# Nixie_PSU.net
KiCad netlist of a schematic drawn in EAGLE
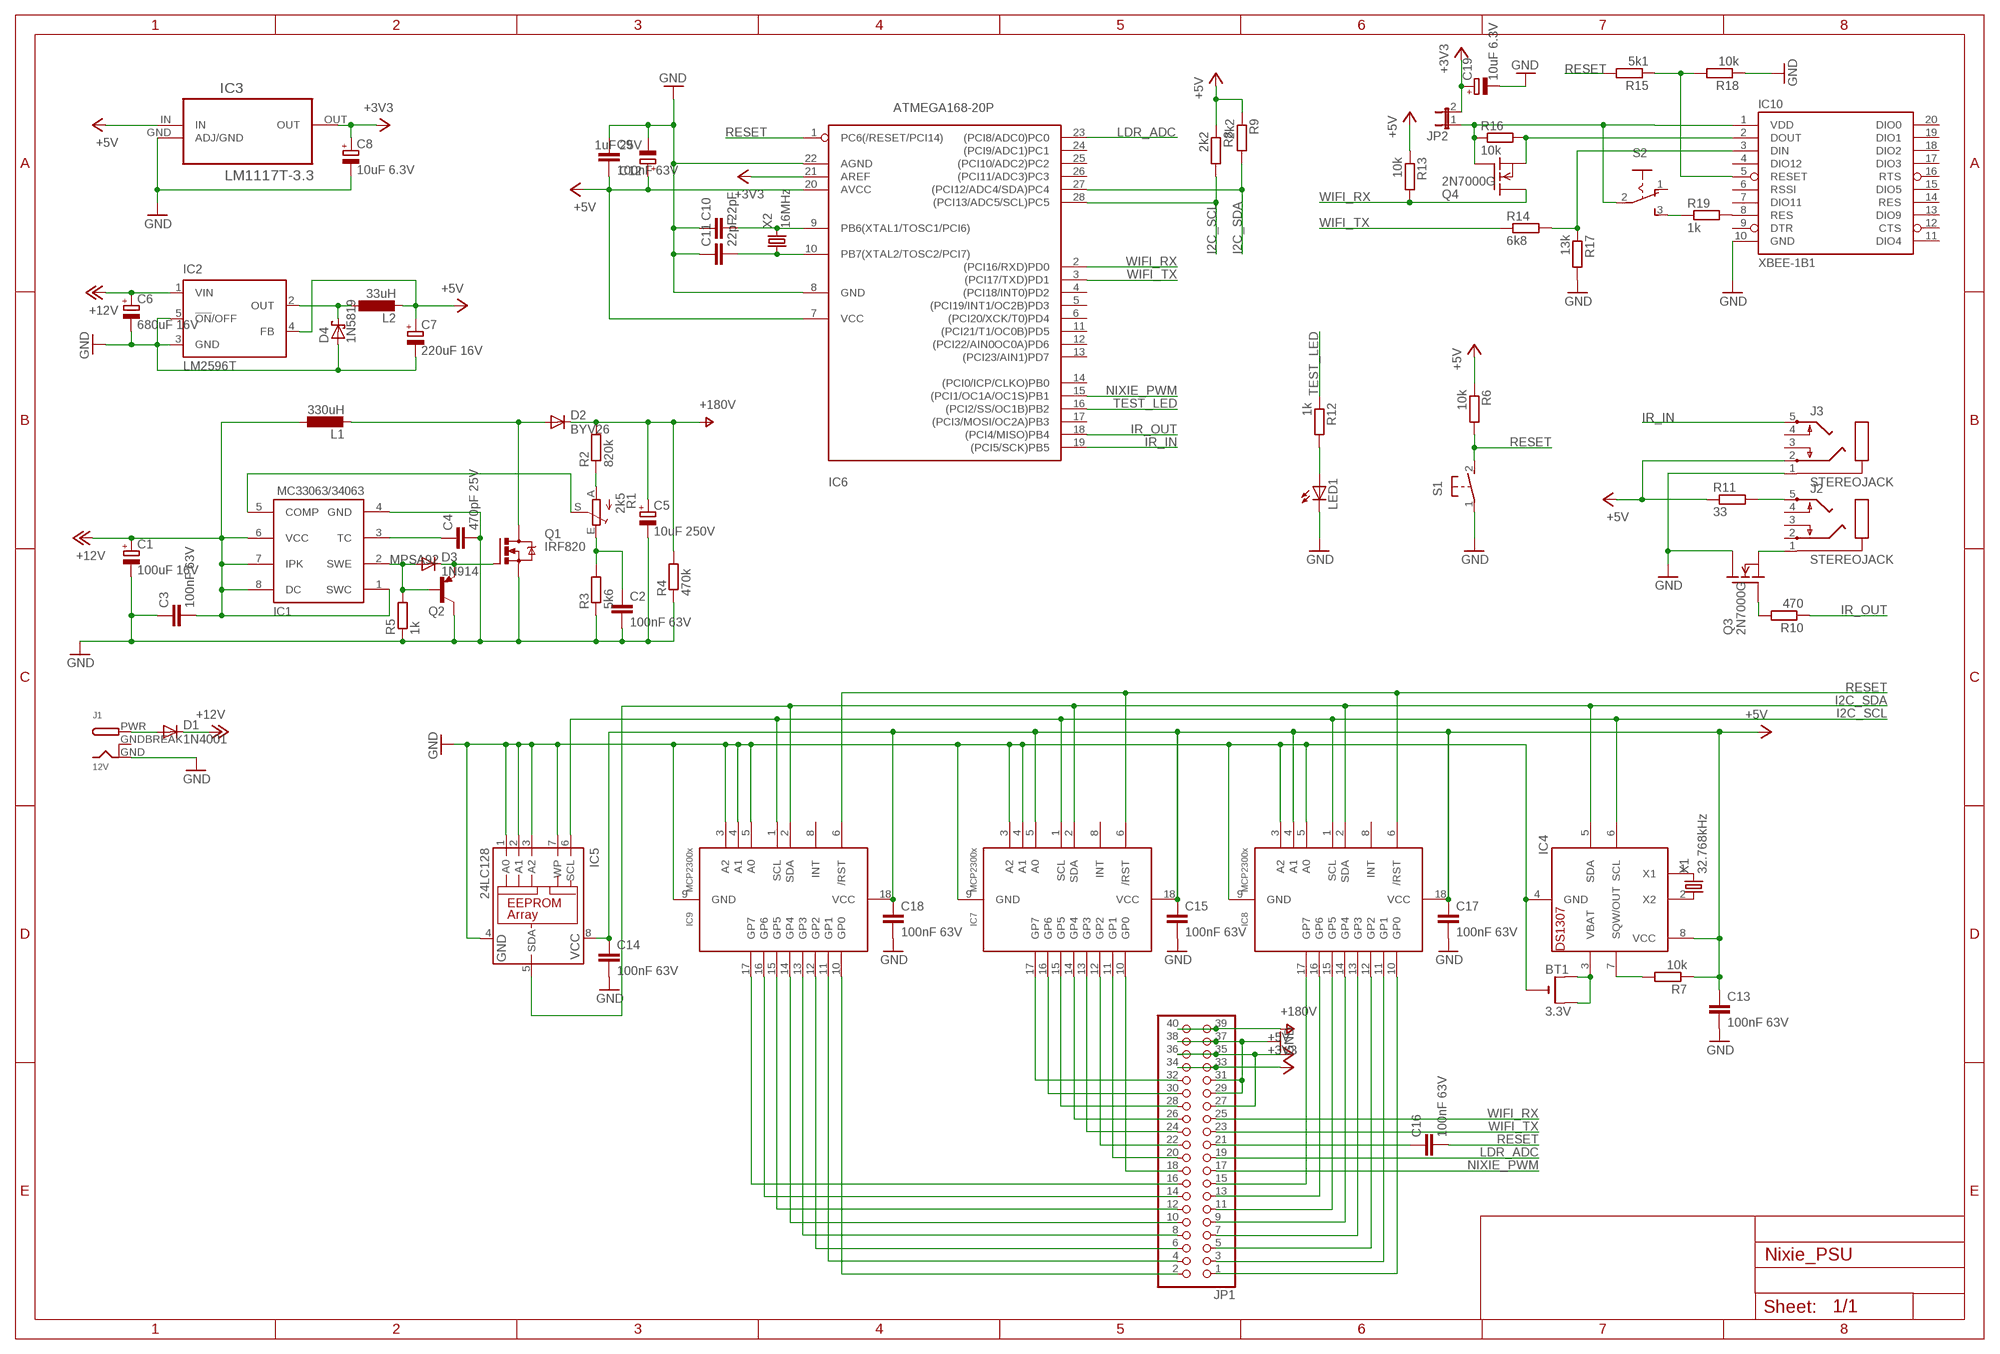
[diagram p0: schematic, sheet 1]

(export (version "E")
  (design (tool "Eeschema 10.0.6"))
  (components
    (comp (ref "BT1")
      (value "3.3V")
      (footprint "eagle-import:CR1220-THM")
      (libsource (lib "eagle-import") (part "CR1220THM"))
    )
    (comp (ref "C1")
      (value "100uF 16V")
      (footprint "eagle-import:E2-5")
      (libsource (lib "eagle-import") (part "CPOL-EUE2-5"))
    )
    (comp (ref "C2")
      (value "100nF 63V")
      (footprint "eagle-import:C050-025X075")
      (libsource (lib "eagle-import") (part "C-EU050-025X075"))
    )
    (comp (ref "C3")
      (value "100nF 63V")
      (footprint "eagle-import:C050-025X075")
      (libsource (lib "eagle-import") (part "C-EU050-025X075"))
    )
    (comp (ref "C4")
      (value "470pF 25V")
      (footprint "eagle-import:C025-025X050")
      (libsource (lib "eagle-import") (part "C-EU025-025X050"))
    )
    (comp (ref "C5")
      (value "10uF 250V")
      (footprint "eagle-import:E5-10,5")
      (libsource (lib "eagle-import") (part "CPOL-EUE5-10.5"))
    )
    (comp (ref "C6")
      (value "680uF 16V")
      (footprint "eagle-import:E3,5-8")
      (libsource (lib "eagle-import") (part "CPOL-EUE3.5-8"))
    )
    (comp (ref "C7")
      (value "220uF 16V")
      (footprint "eagle-import:E2,5-7")
      (libsource (lib "eagle-import") (part "CPOL-EUE2.5-7"))
    )
    (comp (ref "C8")
      (value "10uF 6.3V")
      (footprint "eagle-import:E5-4")
      (libsource (lib "eagle-import") (part "CPOL-EUE5-4"))
    )
    (comp (ref "C9")
      (value "100nF 63V")
      (footprint "eagle-import:C050-025X075")
      (libsource (lib "eagle-import") (part "C-EU050-025X075"))
    )
    (comp (ref "C10")
      (value "22pF")
      (footprint "eagle-import:C025-025X050")
      (libsource (lib "eagle-import") (part "C-EU025-025X050"))
    )
    (comp (ref "C11")
      (value "22pF")
      (footprint "eagle-import:C025-025X050")
      (libsource (lib "eagle-import") (part "C-EU025-025X050"))
    )
    (comp (ref "C12")
      (value "1uF 25V")
      (footprint "eagle-import:E5-4")
      (libsource (lib "eagle-import") (part "CPOL-EUE5-4"))
    )
    (comp (ref "C13")
      (value "100nF 63V")
      (footprint "eagle-import:C050-025X075")
      (libsource (lib "eagle-import") (part "C-EU050-025X075"))
    )
    (comp (ref "C14")
      (value "100nF 63V")
      (footprint "eagle-import:C050-025X075")
      (libsource (lib "eagle-import") (part "C-EU050-025X075"))
    )
    (comp (ref "C15")
      (value "100nF 63V")
      (footprint "eagle-import:C050-025X075")
      (libsource (lib "eagle-import") (part "C-EU050-025X075"))
    )
    (comp (ref "C16")
      (value "100nF 63V")
      (footprint "eagle-import:C050-025X075")
      (libsource (lib "eagle-import") (part "C-EU050-025X075"))
    )
    (comp (ref "C17")
      (value "100nF 63V")
      (footprint "eagle-import:C050-025X075")
      (libsource (lib "eagle-import") (part "C-EU050-025X075"))
    )
    (comp (ref "C18")
      (value "100nF 63V")
      (footprint "eagle-import:C050-025X075")
      (libsource (lib "eagle-import") (part "C-EU050-025X075"))
    )
    (comp (ref "C19")
      (value "10uF 6.3V")
      (footprint "eagle-import:E5-4")
      (libsource (lib "eagle-import") (part "CPOL-EUE5-4"))
    )
    (comp (ref "D1")
      (value "1N4001")
      (footprint "eagle-import:DO41-10")
      (libsource (lib "eagle-import") (part "1N4004"))
    )
    (comp (ref "D2")
      (value "BYV26")
      (footprint "eagle-import:SOD57-10")
      (libsource (lib "eagle-import") (part "BYV27"))
    )
    (comp (ref "D3")
      (value "1N914")
      (footprint "eagle-import:DO34-7")
      (libsource (lib "eagle-import") (part "DIODE-DO34-7"))
    )
    (comp (ref "D4")
      (value "1N5819")
      (footprint "eagle-import:DO41-10")
      (libsource (lib "eagle-import") (part "SCHOTTKY-DIODEDO41"))
    )
    (comp (ref "IC1")
      (value "MC33063/MC34063P")
      (footprint "eagle-import:DIL08")
      (libsource (lib "eagle-import") (part "MC33063/MC34063P"))
    )
    (comp (ref "IC2")
      (value "LM2596T")
      (footprint "eagle-import:T05D")
      (fields (field (name "MPN") "LM2596T-ADJ/LF02"))
      (libsource (lib "eagle-import") (part "LM2596T"))
    )
    (comp (ref "IC3")
      (value "LM1117T-3.3")
      (footprint "eagle-import:TO220BV")
      (libsource (lib "eagle-import") (part "LM1117T-3.3"))
    )
    (comp (ref "IC4")
      (value "DS1307")
      (footprint "eagle-import:DIL08")
      (libsource (lib "eagle-import") (part "DS1307"))
    )
    (comp (ref "IC5")
      (value "24LC128")
      (footprint "eagle-import:DIL08")
      (libsource (lib "eagle-import") (part "24"))
    )
    (comp (ref "IC6")
      (value "ATMEGA168-20P")
      (footprint "eagle-import:DIL28-3")
      (libsource (lib "eagle-import") (part "ATMEGA168P-20"))
    )
    (comp (ref "IC7")
      (value "MCP2300X/P")
      (footprint "eagle-import:DIL18")
      (libsource (lib "eagle-import") (part "MCP2300X/P"))
    )
    (comp (ref "IC8")
      (value "MCP2300X/P")
      (footprint "eagle-import:DIL18")
      (libsource (lib "eagle-import") (part "MCP2300X/P"))
    )
    (comp (ref "IC9")
      (value "MCP2300X/P")
      (footprint "eagle-import:DIL18")
      (libsource (lib "eagle-import") (part "MCP2300X/P"))
    )
    (comp (ref "IC10")
      (value "XBEE-1B1")
      (footprint "eagle-import:XBEE-1")
      (libsource (lib "eagle-import") (part "XBEE-1B1"))
    )
    (comp (ref "J1")
      (value "12V")
      (footprint "eagle-import:DCJACK_2MM_PTH")
      (libsource (lib "eagle-import") (part "DCBARRELPTH"))
    )
    (comp (ref "J2")
      (value "STEREOJACK")
      (footprint "eagle-import:STX3100")
      (libsource (lib "eagle-import") (part "STEREOJACK"))
    )
    (comp (ref "J3")
      (value "STEREOJACK")
      (footprint "eagle-import:STX3100")
      (libsource (lib "eagle-import") (part "STEREOJACK"))
    )
    (comp (ref "JP1")
      (value "PINHD-2X20")
      (footprint "eagle-import:2X20")
      (libsource (lib "eagle-import") (part "PINHD-2X20"))
    )
    (comp (ref "JP2")
      (value "JP1E")
      (footprint "eagle-import:JP1")
      (libsource (lib "eagle-import") (part "JP1E"))
    )
    (comp (ref "L1")
      (value "330uH")
      (footprint "eagle-import:0207_5V")
      (libsource (lib "eagle-import") (part "L-EU0207/5V"))
    )
    (comp (ref "L2")
      (value "33uH")
      (footprint "eagle-import:0207_5V")
      (libsource (lib "eagle-import") (part "L-EU0207/5V"))
    )
    (comp (ref "LED1")
      (value "LED5MM")
      (footprint "eagle-import:LED5MM")
      (libsource (lib "eagle-import") (part "LED5MM"))
    )
    (comp (ref "Q1")
      (value "IRF820")
      (footprint "eagle-import:TO220BV")
      (libsource (lib "eagle-import") (part "IRF540"))
    )
    (comp (ref "Q2")
      (value "MPSA92")
      (footprint "eagle-import:TO92")
      (libsource (lib "eagle-import") (part "-PNP-TO92"))
    )
    (comp (ref "Q3")
      (value "2N7000G")
      (footprint "eagle-import:TO-92")
      (libsource (lib "eagle-import") (part "TN0604N3"))
    )
    (comp (ref "Q4")
      (value "2N7000G")
      (footprint "eagle-import:TO-92")
      (libsource (lib "eagle-import") (part "TN0604N3"))
    )
    (comp (ref "R1")
      (value "2k5")
      (footprint "eagle-import:RJ9W")
      (libsource (lib "eagle-import") (part "TRIM_EU-RJ9W"))
    )
    (comp (ref "R2")
      (value "820k")
      (footprint "eagle-import:0207_10")
      (libsource (lib "eagle-import") (part "R-EU_0207/10"))
    )
    (comp (ref "R3")
      (value "5k6")
      (footprint "eagle-import:0207_10")
      (libsource (lib "eagle-import") (part "R-EU_0207/10"))
    )
    (comp (ref "R4")
      (value "470k")
      (footprint "eagle-import:0207_10")
      (libsource (lib "eagle-import") (part "R-EU_0207/10"))
    )
    (comp (ref "R5")
      (value "1k")
      (footprint "eagle-import:0207_10")
      (libsource (lib "eagle-import") (part "R-EU_0207/10"))
    )
    (comp (ref "R6")
      (value "10k")
      (footprint "eagle-import:0207_10")
      (libsource (lib "eagle-import") (part "R-EU_0207/10"))
    )
    (comp (ref "R7")
      (value "10k")
      (footprint "eagle-import:0207_10")
      (libsource (lib "eagle-import") (part "R-EU_0207/10"))
    )
    (comp (ref "R8")
      (value "2k2")
      (footprint "eagle-import:0207_10")
      (libsource (lib "eagle-import") (part "R-EU_0207/10"))
    )
    (comp (ref "R9")
      (value "2k2")
      (footprint "eagle-import:0207_10")
      (libsource (lib "eagle-import") (part "R-EU_0207/10"))
    )
    (comp (ref "R10")
      (value "470")
      (footprint "eagle-import:0207_10")
      (libsource (lib "eagle-import") (part "R-EU_0207/10"))
    )
    (comp (ref "R11")
      (value "33")
      (footprint "eagle-import:0207_10")
      (libsource (lib "eagle-import") (part "R-EU_0207/10"))
    )
    (comp (ref "R12")
      (value "1k")
      (footprint "eagle-import:0207_10")
      (libsource (lib "eagle-import") (part "R-EU_0207/10"))
    )
    (comp (ref "R13")
      (value "10k")
      (footprint "eagle-import:0207_10")
      (libsource (lib "eagle-import") (part "R-EU_0207/10"))
    )
    (comp (ref "R14")
      (value "6k8")
      (footprint "eagle-import:0207_10")
      (libsource (lib "eagle-import") (part "R-EU_0207/10"))
    )
    (comp (ref "R15")
      (value "5k1")
      (footprint "eagle-import:0207_10")
      (libsource (lib "eagle-import") (part "R-EU_0207/10"))
    )
    (comp (ref "R16")
      (value "10k")
      (footprint "eagle-import:0207_10")
      (libsource (lib "eagle-import") (part "R-EU_0207/10"))
    )
    (comp (ref "R17")
      (value "13k")
      (footprint "eagle-import:0207_10")
      (libsource (lib "eagle-import") (part "R-EU_0207/10"))
    )
    (comp (ref "R18")
      (value "10k")
      (footprint "eagle-import:0207_10")
      (libsource (lib "eagle-import") (part "R-EU_0207/10"))
    )
    (comp (ref "R19")
      (value "1k")
      (footprint "eagle-import:0207_10")
      (libsource (lib "eagle-import") (part "R-EU_0207/10"))
    )
    (comp (ref "S1")
      (value "31-XX")
      (footprint "eagle-import:B3F-31XX")
      (libsource (lib "eagle-import") (part "31-XX"))
    )
    (comp (ref "S2")
      (value "M251")
      (footprint "eagle-import:M251")
      (libsource (lib "eagle-import") (part "M251"))
    )
    (comp (ref "X1")
      (value "32.768kHz")
      (footprint "eagle-import:TC38H")
      (libsource (lib "eagle-import") (part "CRYSTALTC38H"))
    )
    (comp (ref "X2")
      (value "16MHz")
      (footprint "eagle-import:HC18U-V")
      (libsource (lib "eagle-import") (part "CRYSTALHC18U-V"))
    )
  )
  (nets
    (net (code "1") (name "+3V3") (class "Default")
      (node (ref "C19") (pin "+") (pinfunction "+_+") (pintype "passive"))
      (node (ref "C8") (pin "+") (pinfunction "+_+") (pintype "passive"))
      (node (ref "IC3") (pin "OUT") (pinfunction "OUT_OUT") (pintype "output"))
      (node (ref "IC6") (pin "21") (pinfunction "AREF_21") (pintype "bidirectional"))
      (node (ref "JP1") (pin "33") (pinfunction "33_33") (pintype "passive"))
      (node (ref "JP1") (pin "34") (pinfunction "34_34") (pintype "passive"))
      (node (ref "JP2") (pin "2") (pinfunction "2_2") (pintype "passive"))
    )
    (net (code "2") (name "+5V") (class "Default")
      (node (ref "C12") (pin "+") (pinfunction "+_+") (pintype "passive"))
      (node (ref "C13") (pin "1") (pinfunction "1_1") (pintype "passive"))
      (node (ref "C14") (pin "1") (pinfunction "1_1") (pintype "passive"))
      (node (ref "C15") (pin "1") (pinfunction "1_1") (pintype "passive"))
      (node (ref "C17") (pin "1") (pinfunction "1_1") (pintype "passive"))
      (node (ref "C18") (pin "1") (pinfunction "1_1") (pintype "passive"))
      (node (ref "C7") (pin "+") (pinfunction "+_+") (pintype "passive"))
      (node (ref "C9") (pin "2") (pinfunction "2_2") (pintype "passive"))
      (node (ref "IC2") (pin "4") (pinfunction "FB_4") (pintype "input"))
      (node (ref "IC3") (pin "IN") (pinfunction "IN_IN") (pintype "input"))
      (node (ref "IC4") (pin "8") (pinfunction "VCC_8") (pintype "power_in"))
      (node (ref "IC5") (pin "8") (pinfunction "VCC_8") (pintype "power_in"))
      (node (ref "IC6") (pin "20") (pinfunction "AVCC_20") (pintype "bidirectional"))
      (node (ref "IC6") (pin "7") (pinfunction "VCC_7") (pintype "bidirectional"))
      (node (ref "IC7") (pin "18") (pinfunction "VCC_18") (pintype "power_in"))
      (node (ref "IC7") (pin "5") (pinfunction "A0_5") (pintype "input"))
      (node (ref "IC8") (pin "18") (pinfunction "VCC_18") (pintype "power_in"))
      (node (ref "IC8") (pin "4") (pinfunction "A1_4") (pintype "input"))
      (node (ref "IC9") (pin "18") (pinfunction "VCC_18") (pintype "power_in"))
      (node (ref "J3") (pin "2") (pinfunction "2_2") (pintype "passive"))
      (node (ref "JP1") (pin "27") (pinfunction "27_27") (pintype "passive"))
      (node (ref "JP1") (pin "35") (pinfunction "35_35") (pintype "passive"))
      (node (ref "JP1") (pin "36") (pinfunction "36_36") (pintype "passive"))
      (node (ref "L2") (pin "2") (pinfunction "2_2") (pintype "passive"))
      (node (ref "R11") (pin "1") (pinfunction "1_1") (pintype "passive"))
      (node (ref "R13") (pin "1") (pinfunction "1_1") (pintype "passive"))
      (node (ref "R6") (pin "1") (pinfunction "1_1") (pintype "passive"))
      (node (ref "R7") (pin "1") (pinfunction "1_1") (pintype "passive"))
      (node (ref "R8") (pin "1") (pinfunction "1_1") (pintype "passive"))
      (node (ref "R9") (pin "1") (pinfunction "1_1") (pintype "passive"))
    )
    (net (code "3") (name "+12V") (class "Default")
      (node (ref "C1") (pin "+") (pinfunction "+_+") (pintype "passive"))
      (node (ref "C3") (pin "2") (pinfunction "2_2") (pintype "passive"))
      (node (ref "C6") (pin "+") (pinfunction "+_+") (pintype "passive"))
      (node (ref "D1") (pin "C") (pinfunction "C_C") (pintype "passive"))
      (node (ref "IC1") (pin "1") (pinfunction "SWC_1") (pintype "input"))
      (node (ref "IC1") (pin "6") (pinfunction "VCC_6") (pintype "power_in"))
      (node (ref "IC1") (pin "7") (pinfunction "IPK_7") (pintype "bidirectional"))
      (node (ref "IC1") (pin "8") (pinfunction "DC_8") (pintype "input"))
      (node (ref "IC2") (pin "1") (pinfunction "VIN_1") (pintype "input"))
      (node (ref "L1") (pin "1") (pinfunction "1_1") (pintype "passive"))
    )
    (net (code "4") (name "+180V") (class "Default")
      (node (ref "C5") (pin "+") (pinfunction "+_+") (pintype "passive"))
      (node (ref "D2") (pin "C") (pinfunction "C_C") (pintype "passive"))
      (node (ref "JP1") (pin "39") (pinfunction "39_39") (pintype "passive"))
      (node (ref "JP1") (pin "40") (pinfunction "40_40") (pintype "passive"))
      (node (ref "R2") (pin "2") (pinfunction "2_2") (pintype "passive"))
      (node (ref "R4") (pin "2") (pinfunction "2_2") (pintype "passive"))
    )
    (net (code "5") (name "/GNDBREAK") (class "Default")
      (node (ref "J1") (pin "GNDBREAK") (pinfunction "GNDBREAK_GNDBREAK") (pintype "power_in"))
    )
    (net (code "6") (name "/I2C_SCL") (class "Default")
      (node (ref "IC4") (pin "6") (pinfunction "SCL_6") (pintype "bidirectional"))
      (node (ref "IC5") (pin "6") (pinfunction "SCL_6") (pintype "input"))
      (node (ref "IC6") (pin "28") (pinfunction "(PCI13/ADC5/SCL)PC5_28") (pintype "bidirectional"))
      (node (ref "IC7") (pin "1") (pinfunction "SCL_1") (pintype "bidirectional"))
      (node (ref "IC8") (pin "1") (pinfunction "SCL_1") (pintype "bidirectional"))
      (node (ref "IC9") (pin "1") (pinfunction "SCL_1") (pintype "bidirectional"))
      (node (ref "R8") (pin "2") (pinfunction "2_2") (pintype "passive"))
    )
    (net (code "7") (name "/I2C_SDA") (class "Default")
      (node (ref "IC4") (pin "5") (pinfunction "SDA_5") (pintype "bidirectional"))
      (node (ref "IC5") (pin "5") (pinfunction "SDA_5") (pintype "bidirectional"))
      (node (ref "IC6") (pin "27") (pinfunction "(PCI12/ADC4/SDA)PC4_27") (pintype "bidirectional"))
      (node (ref "IC7") (pin "2") (pinfunction "SDA_2") (pintype "bidirectional"))
      (node (ref "IC8") (pin "2") (pinfunction "SDA_2") (pintype "bidirectional"))
      (node (ref "IC9") (pin "2") (pinfunction "SDA_2") (pintype "bidirectional"))
      (node (ref "R9") (pin "2") (pinfunction "2_2") (pintype "passive"))
    )
    (net (code "8") (name "/IR_IN") (class "Default")
      (node (ref "IC6") (pin "19") (pinfunction "(PCI5/SCK)PB5_19") (pintype "bidirectional"))
      (node (ref "J3") (pin "5") (pinfunction "5_5") (pintype "passive"))
    )
    (net (code "9") (name "/IR_OUT") (class "Default")
      (node (ref "IC6") (pin "18") (pinfunction "(PCI4/MISO)PB4_18") (pintype "bidirectional"))
      (node (ref "R10") (pin "1") (pinfunction "1_1") (pintype "passive"))
    )
    (net (code "10") (name "/LDR_ADC") (class "Default")
      (node (ref "IC6") (pin "23") (pinfunction "(PCI8/ADC0)PC0_23") (pintype "bidirectional"))
      (node (ref "JP1") (pin "19") (pinfunction "19_19") (pintype "passive"))
    )
    (net (code "11") (name "/NIXIE_PWM") (class "Default")
      (node (ref "IC6") (pin "15") (pinfunction "(PCI1/OC1A/OC1S)PB1_15") (pintype "bidirectional"))
      (node (ref "JP1") (pin "17") (pinfunction "17_17") (pintype "passive"))
    )
    (net (code "12") (name "/RESET") (class "Default")
      (node (ref "C16") (pin "2") (pinfunction "2_2") (pintype "passive"))
      (node (ref "IC6") (pin "1") (pinfunction "PC6(/RESET/PCI14)_1") (pintype "bidirectional"))
      (node (ref "IC7") (pin "6") (pinfunction "/RST_6") (pintype "input"))
      (node (ref "IC8") (pin "6") (pinfunction "/RST_6") (pintype "input"))
      (node (ref "IC9") (pin "6") (pinfunction "/RST_6") (pintype "input"))
      (node (ref "R15") (pin "2") (pinfunction "2_2") (pintype "passive"))
      (node (ref "R6") (pin "2") (pinfunction "2_2") (pintype "passive"))
      (node (ref "S1") (pin "2") (pinfunction "S_2") (pintype "passive"))
    )
    (net (code "13") (name "/TEST_LED") (class "Default")
      (node (ref "IC6") (pin "16") (pinfunction "(PCI2/SS/OC1B)PB2_16") (pintype "bidirectional"))
      (node (ref "R12") (pin "1") (pinfunction "1_1") (pintype "passive"))
    )
    (net (code "14") (name "/WIFI_RX") (class "Default")
      (node (ref "IC6") (pin "2") (pinfunction "(PCI16/RXD)PD0_2") (pintype "bidirectional"))
      (node (ref "JP1") (pin "25") (pinfunction "25_25") (pintype "passive"))
      (node (ref "Q4") (pin "3") (pinfunction "D_3") (pintype "passive"))
      (node (ref "R13") (pin "2") (pinfunction "2_2") (pintype "passive"))
    )
    (net (code "15") (name "/WIFI_TX") (class "Default")
      (node (ref "IC6") (pin "3") (pinfunction "(PCI17/TXD)PD1_3") (pintype "bidirectional"))
      (node (ref "JP1") (pin "23") (pinfunction "23_23") (pintype "passive"))
      (node (ref "R14") (pin "1") (pinfunction "1_1") (pintype "passive"))
    )
    (net (code "16") (name "GND") (class "Default")
      (node (ref "BT1") (pin "-") (pinfunction "-_-") (pintype "passive"))
      (node (ref "C1") (pin "-") (pinfunction "-_-") (pintype "passive"))
      (node (ref "C10") (pin "1") (pinfunction "1_1") (pintype "passive"))
      (node (ref "C11") (pin "1") (pinfunction "1_1") (pintype "passive"))
      (node (ref "C12") (pin "-") (pinfunction "-_-") (pintype "passive"))
      (node (ref "C13") (pin "2") (pinfunction "2_2") (pintype "passive"))
      (node (ref "C14") (pin "2") (pinfunction "2_2") (pintype "passive"))
      (node (ref "C15") (pin "2") (pinfunction "2_2") (pintype "passive"))
      (node (ref "C17") (pin "2") (pinfunction "2_2") (pintype "passive"))
      (node (ref "C18") (pin "2") (pinfunction "2_2") (pintype "passive"))
      (node (ref "C19") (pin "-") (pinfunction "-_-") (pintype "passive"))
      (node (ref "C2") (pin "2") (pinfunction "2_2") (pintype "passive"))
      (node (ref "C3") (pin "1") (pinfunction "1_1") (pintype "passive"))
      (node (ref "C4") (pin "2") (pinfunction "2_2") (pintype "passive"))
      (node (ref "C5") (pin "-") (pinfunction "-_-") (pintype "passive"))
      (node (ref "C6") (pin "-") (pinfunction "-_-") (pintype "passive"))
      (node (ref "C7") (pin "-") (pinfunction "-_-") (pintype "passive"))
      (node (ref "C8") (pin "-") (pinfunction "-_-") (pintype "passive"))
      (node (ref "C9") (pin "1") (pinfunction "1_1") (pintype "passive"))
      (node (ref "D4") (pin "A") (pinfunction "A_A") (pintype "passive"))
      (node (ref "IC1") (pin "4") (pinfunction "GND_4") (pintype "power_in"))
      (node (ref "IC10") (pin "10") (pinfunction "GND_10") (pintype "power_in"))
      (node (ref "IC2") (pin "3") (pinfunction "GND_3") (pintype "power_in"))
      (node (ref "IC2") (pin "5") (pinfunction "~{ON}/OFF_5") (pintype "input"))
      (node (ref "IC3") (pin "GND") (pinfunction "ADJ/GND_GND") (pintype "passive"))
      (node (ref "IC4") (pin "4") (pinfunction "GND_4") (pintype "power_in"))
      (node (ref "IC5") (pin "1") (pinfunction "A0_1") (pintype "input"))
      (node (ref "IC5") (pin "2") (pinfunction "A1_2") (pintype "input"))
      (node (ref "IC5") (pin "3") (pinfunction "A2_3") (pintype "input"))
      (node (ref "IC5") (pin "4") (pinfunction "GND_4") (pintype "power_in"))
      (node (ref "IC5") (pin "7") (pinfunction "WP_7") (pintype "input"))
      (node (ref "IC6") (pin "22") (pinfunction "AGND_22") (pintype "bidirectional"))
      (node (ref "IC6") (pin "8") (pinfunction "GND_8") (pintype "bidirectional"))
      (node (ref "IC7") (pin "3") (pinfunction "A2_3") (pintype "input"))
      (node (ref "IC7") (pin "4") (pinfunction "A1_4") (pintype "input"))
      (node (ref "IC7") (pin "9") (pinfunction "GND_9") (pintype "power_in"))
      (node (ref "IC8") (pin "3") (pinfunction "A2_3") (pintype "input"))
      (node (ref "IC8") (pin "5") (pinfunction "A0_5") (pintype "input"))
      (node (ref "IC8") (pin "9") (pinfunction "GND_9") (pintype "power_in"))
      (node (ref "IC9") (pin "3") (pinfunction "A2_3") (pintype "input"))
      (node (ref "IC9") (pin "4") (pinfunction "A1_4") (pintype "input"))
      (node (ref "IC9") (pin "5") (pinfunction "A0_5") (pintype "input"))
      (node (ref "IC9") (pin "9") (pinfunction "GND_9") (pintype "power_in"))
      (node (ref "J1") (pin "GND") (pinfunction "GND_GND") (pintype "power_in"))
      (node (ref "J3") (pin "1") (pinfunction "1_1") (pintype "passive"))
      (node (ref "JP1") (pin "29") (pinfunction "29_29") (pintype "passive"))
      (node (ref "JP1") (pin "31") (pinfunction "31_31") (pintype "passive"))
      (node (ref "JP1") (pin "37") (pinfunction "37_37") (pintype "passive"))
      (node (ref "JP1") (pin "38") (pinfunction "38_38") (pintype "passive"))
      (node (ref "LED1") (pin "K") (pinfunction "C_K") (pintype "passive"))
      (node (ref "Q1") (pin "S") (pinfunction "S_S") (pintype "passive"))
      (node (ref "Q2") (pin "3") (pinfunction "C_3") (pintype "passive"))
      (node (ref "Q3") (pin "3") (pinfunction "D_3") (pintype "passive"))
      (node (ref "R17") (pin "2") (pinfunction "2_2") (pintype "passive"))
      (node (ref "R18") (pin "1") (pinfunction "1_1") (pintype "passive"))
      (node (ref "R3") (pin "1") (pinfunction "1_1") (pintype "passive"))
      (node (ref "R4") (pin "1") (pinfunction "1_1") (pintype "passive"))
      (node (ref "R5") (pin "1") (pinfunction "1_1") (pintype "passive"))
      (node (ref "S1") (pin "1") (pinfunction "P_1") (pintype "passive"))
    )
    (net (code "17") (name "Net-(BT1-+)") (class "Default")
      (node (ref "BT1") (pin "+1") (pinfunction "+_+1") (pintype "passive"))
      (node (ref "BT1") (pin "+2") (pinfunction "+1_+2") (pintype "passive"))
      (node (ref "IC4") (pin "3") (pinfunction "VBAT_3") (pintype "power_in"))
    )
    (net (code "18") (name "Net-(C2-Pad1)") (class "Default")
      (node (ref "C2") (pin "1") (pinfunction "1_1") (pintype "passive"))
      (node (ref "R1") (pin "E") (pinfunction "E_E") (pintype "passive"))
      (node (ref "R3") (pin "2") (pinfunction "2_2") (pintype "passive"))
    )
    (net (code "19") (name "Net-(C16-Pad1)") (class "Default")
      (node (ref "C16") (pin "1") (pinfunction "1_1") (pintype "passive"))
      (node (ref "JP1") (pin "21") (pinfunction "21_21") (pintype "passive"))
    )
    (net (code "20") (name "Net-(D1-PadA)") (class "Default")
      (node (ref "D1") (pin "A") (pinfunction "A_A") (pintype "passive"))
      (node (ref "J1") (pin "PWR") (pinfunction "PWR_PWR") (pintype "power_in"))
    )
    (net (code "21") (name "Net-(D2-PadA)") (class "Default")
      (node (ref "D2") (pin "A") (pinfunction "A_A") (pintype "passive"))
      (node (ref "L1") (pin "2") (pinfunction "2_2") (pintype "passive"))
      (node (ref "Q1") (pin "D") (pinfunction "D_D") (pintype "passive"))
    )
    (net (code "22") (name "Net-(IC1-COMP)") (class "Default")
      (node (ref "IC1") (pin "5") (pinfunction "COMP_5") (pintype "input"))
      (node (ref "R1") (pin "S") (pinfunction "S_S") (pintype "passive"))
    )
    (net (code "23") (name "Net-(IC1-SWE)") (class "Default")
      (node (ref "D3") (pin "A") (pinfunction "A_A") (pintype "passive"))
      (node (ref "IC1") (pin "2") (pinfunction "SWE_2") (pintype "input"))
      (node (ref "Q2") (pin "2") (pinfunction "B_2") (pintype "passive"))
      (node (ref "R5") (pin "2") (pinfunction "2_2") (pintype "passive"))
    )
    (net (code "24") (name "Net-(IC1-TC)") (class "Default")
      (node (ref "C4") (pin "1") (pinfunction "1_1") (pintype "passive"))
      (node (ref "IC1") (pin "3") (pinfunction "TC_3") (pintype "input"))
    )
    (net (code "25") (name "Net-(IC2-OUT)") (class "Default")
      (node (ref "D4") (pin "C") (pinfunction "C_C") (pintype "passive"))
      (node (ref "IC2") (pin "2") (pinfunction "OUT_2") (pintype "output"))
      (node (ref "L2") (pin "1") (pinfunction "1_1") (pintype "passive"))
    )
    (net (code "26") (name "Net-(IC4-SQW{slash}OUT)") (class "Default")
      (node (ref "IC4") (pin "7") (pinfunction "SQW/OUT_7") (pintype "bidirectional"))
      (node (ref "R7") (pin "2") (pinfunction "2_2") (pintype "passive"))
    )
    (net (code "27") (name "Net-(IC4-X1)") (class "Default")
      (node (ref "IC4") (pin "1") (pinfunction "X1_1") (pintype "passive"))
      (node (ref "X1") (pin "2") (pinfunction "2_2") (pintype "passive"))
    )
    (net (code "28") (name "Net-(IC4-X2)") (class "Default")
      (node (ref "IC4") (pin "2") (pinfunction "X2_2") (pintype "passive"))
      (node (ref "X1") (pin "1") (pinfunction "1_1") (pintype "passive"))
    )
    (net (code "29") (name "Net-(IC6-PB6(XTAL1{slash}TOSC1{slash}PCI6))") (class "Default")
      (node (ref "C10") (pin "2") (pinfunction "2_2") (pintype "passive"))
      (node (ref "IC6") (pin "9") (pinfunction "PB6(XTAL1/TOSC1/PCI6)_9") (pintype "bidirectional"))
      (node (ref "X2") (pin "2") (pinfunction "2_2") (pintype "passive"))
    )
    (net (code "30") (name "Net-(IC6-PB7(XTAL2{slash}TOSC2{slash}PCI7))") (class "Default")
      (node (ref "C11") (pin "2") (pinfunction "2_2") (pintype "passive"))
      (node (ref "IC6") (pin "10") (pinfunction "PB7(XTAL2/TOSC2/PCI7)_10") (pintype "bidirectional"))
      (node (ref "X2") (pin "1") (pinfunction "1_1") (pintype "passive"))
    )
    (net (code "31") (name "Net-(IC7-GP0)") (class "Default")
      (node (ref "IC7") (pin "10") (pinfunction "GP0_10") (pintype "bidirectional"))
      (node (ref "JP1") (pin "18") (pinfunction "18_18") (pintype "passive"))
    )
    (net (code "32") (name "Net-(IC7-GP1)") (class "Default")
      (node (ref "IC7") (pin "11") (pinfunction "GP1_11") (pintype "bidirectional"))
      (node (ref "JP1") (pin "20") (pinfunction "20_20") (pintype "passive"))
    )
    (net (code "33") (name "Net-(IC7-GP2)") (class "Default")
      (node (ref "IC7") (pin "12") (pinfunction "GP2_12") (pintype "bidirectional"))
      (node (ref "JP1") (pin "22") (pinfunction "22_22") (pintype "passive"))
    )
    (net (code "34") (name "Net-(IC7-GP3)") (class "Default")
      (node (ref "IC7") (pin "13") (pinfunction "GP3_13") (pintype "bidirectional"))
      (node (ref "JP1") (pin "24") (pinfunction "24_24") (pintype "passive"))
    )
    (net (code "35") (name "Net-(IC7-GP4)") (class "Default")
      (node (ref "IC7") (pin "14") (pinfunction "GP4_14") (pintype "bidirectional"))
      (node (ref "JP1") (pin "26") (pinfunction "26_26") (pintype "passive"))
    )
    (net (code "36") (name "Net-(IC7-GP5)") (class "Default")
      (node (ref "IC7") (pin "15") (pinfunction "GP5_15") (pintype "bidirectional"))
      (node (ref "JP1") (pin "28") (pinfunction "28_28") (pintype "passive"))
    )
    (net (code "37") (name "Net-(IC7-GP6)") (class "Default")
      (node (ref "IC7") (pin "16") (pinfunction "GP6_16") (pintype "bidirectional"))
      (node (ref "JP1") (pin "30") (pinfunction "30_30") (pintype "passive"))
    )
    (net (code "38") (name "Net-(IC7-GP7)") (class "Default")
      (node (ref "IC7") (pin "17") (pinfunction "GP7_17") (pintype "bidirectional"))
      (node (ref "JP1") (pin "32") (pinfunction "32_32") (pintype "passive"))
    )
    (net (code "39") (name "Net-(IC8-GP0)") (class "Default")
      (node (ref "IC8") (pin "10") (pinfunction "GP0_10") (pintype "bidirectional"))
      (node (ref "JP1") (pin "1") (pinfunction "1_1") (pintype "passive"))
    )
    (net (code "40") (name "Net-(IC8-GP1)") (class "Default")
      (node (ref "IC8") (pin "11") (pinfunction "GP1_11") (pintype "bidirectional"))
      (node (ref "JP1") (pin "3") (pinfunction "3_3") (pintype "passive"))
    )
    (net (code "41") (name "Net-(IC8-GP2)") (class "Default")
      (node (ref "IC8") (pin "12") (pinfunction "GP2_12") (pintype "bidirectional"))
      (node (ref "JP1") (pin "5") (pinfunction "5_5") (pintype "passive"))
    )
    (net (code "42") (name "Net-(IC8-GP3)") (class "Default")
      (node (ref "IC8") (pin "13") (pinfunction "GP3_13") (pintype "bidirectional"))
      (node (ref "JP1") (pin "7") (pinfunction "7_7") (pintype "passive"))
    )
    (net (code "43") (name "Net-(IC8-GP4)") (class "Default")
      (node (ref "IC8") (pin "14") (pinfunction "GP4_14") (pintype "bidirectional"))
      (node (ref "JP1") (pin "9") (pinfunction "9_9") (pintype "passive"))
    )
    (net (code "44") (name "Net-(IC8-GP5)") (class "Default")
      (node (ref "IC8") (pin "15") (pinfunction "GP5_15") (pintype "bidirectional"))
      (node (ref "JP1") (pin "11") (pinfunction "11_11") (pintype "passive"))
    )
    (net (code "45") (name "Net-(IC8-GP6)") (class "Default")
      (node (ref "IC8") (pin "16") (pinfunction "GP6_16") (pintype "bidirectional"))
      (node (ref "JP1") (pin "13") (pinfunction "13_13") (pintype "passive"))
    )
    (net (code "46") (name "Net-(IC8-GP7)") (class "Default")
      (node (ref "IC8") (pin "17") (pinfunction "GP7_17") (pintype "bidirectional"))
      (node (ref "JP1") (pin "15") (pinfunction "15_15") (pintype "passive"))
    )
    (net (code "47") (name "Net-(IC9-GP0)") (class "Default")
      (node (ref "IC9") (pin "10") (pinfunction "GP0_10") (pintype "bidirectional"))
      (node (ref "JP1") (pin "2") (pinfunction "2_2") (pintype "passive"))
    )
    (net (code "48") (name "Net-(IC9-GP1)") (class "Default")
      (node (ref "IC9") (pin "11") (pinfunction "GP1_11") (pintype "bidirectional"))
      (node (ref "JP1") (pin "4") (pinfunction "4_4") (pintype "passive"))
    )
    (net (code "49") (name "Net-(IC9-GP2)") (class "Default")
      (node (ref "IC9") (pin "12") (pinfunction "GP2_12") (pintype "bidirectional"))
      (node (ref "JP1") (pin "6") (pinfunction "6_6") (pintype "passive"))
    )
    (net (code "50") (name "Net-(IC9-GP3)") (class "Default")
      (node (ref "IC9") (pin "13") (pinfunction "GP3_13") (pintype "bidirectional"))
      (node (ref "JP1") (pin "8") (pinfunction "8_8") (pintype "passive"))
    )
    (net (code "51") (name "Net-(IC9-GP4)") (class "Default")
      (node (ref "IC9") (pin "14") (pinfunction "GP4_14") (pintype "bidirectional"))
      (node (ref "JP1") (pin "10") (pinfunction "10_10") (pintype "passive"))
    )
    (net (code "52") (name "Net-(IC9-GP5)") (class "Default")
      (node (ref "IC9") (pin "15") (pinfunction "GP5_15") (pintype "bidirectional"))
      (node (ref "JP1") (pin "12") (pinfunction "12_12") (pintype "passive"))
    )
    (net (code "53") (name "Net-(IC9-GP6)") (class "Default")
      (node (ref "IC9") (pin "16") (pinfunction "GP6_16") (pintype "bidirectional"))
      (node (ref "JP1") (pin "14") (pinfunction "14_14") (pintype "passive"))
    )
    (net (code "54") (name "Net-(IC9-GP7)") (class "Default")
      (node (ref "IC9") (pin "17") (pinfunction "GP7_17") (pintype "bidirectional"))
      (node (ref "JP1") (pin "16") (pinfunction "16_16") (pintype "passive"))
    )
    (net (code "55") (name "Net-(IC10-DIN)") (class "Default")
      (node (ref "IC10") (pin "3") (pinfunction "DIN_3") (pintype "input"))
      (node (ref "R14") (pin "2") (pinfunction "2_2") (pintype "passive"))
      (node (ref "R17") (pin "1") (pinfunction "1_1") (pintype "passive"))
    )
    (net (code "56") (name "Net-(IC10-DOUT)") (class "Default")
      (node (ref "IC10") (pin "2") (pinfunction "DOUT_2") (pintype "output"))
      (node (ref "Q4") (pin "1") (pinfunction "S_1") (pintype "passive"))
      (node (ref "R16") (pin "2") (pinfunction "2_2") (pintype "passive"))
    )
    (net (code "57") (name "Net-(IC10-RES-Pad8)") (class "Default")
      (node (ref "IC10") (pin "8") (pinfunction "RES_8") (pintype "bidirectional"))
      (node (ref "R19") (pin "2") (pinfunction "2_2") (pintype "passive"))
    )
    (net (code "58") (name "Net-(IC10-RESET)") (class "Default")
      (node (ref "IC10") (pin "5") (pinfunction "RESET_5") (pintype "input"))
      (node (ref "R15") (pin "1") (pinfunction "1_1") (pintype "passive"))
      (node (ref "R18") (pin "2") (pinfunction "2_2") (pintype "passive"))
    )
    (net (code "59") (name "Net-(IC10-VDD)") (class "Default")
      (node (ref "IC10") (pin "1") (pinfunction "VDD_1") (pintype "power_in"))
      (node (ref "JP2") (pin "1") (pinfunction "1_1") (pintype "passive"))
      (node (ref "Q4") (pin "2") (pinfunction "G_2") (pintype "passive"))
      (node (ref "R16") (pin "1") (pinfunction "1_1") (pintype "passive"))
      (node (ref "S2") (pin "2") (pinfunction "P_2") (pintype "passive"))
    )
    (net (code "60") (name "Net-(J2-Pad5)") (class "Default")
      (node (ref "J2") (pin "5") (pinfunction "5_5") (pintype "passive"))
      (node (ref "R11") (pin "2") (pinfunction "2_2") (pintype "passive"))
    )
    (net (code "61") (name "Net-(LED1-PadA)") (class "Default")
      (node (ref "LED1") (pin "A") (pinfunction "A_A") (pintype "passive"))
      (node (ref "R12") (pin "2") (pinfunction "2_2") (pintype "passive"))
    )
    (net (code "62") (name "Net-(Q2-E)") (class "Default")
      (node (ref "D3") (pin "C") (pinfunction "C_C") (pintype "passive"))
      (node (ref "Q1") (pin "G") (pinfunction "G_G") (pintype "passive"))
      (node (ref "Q2") (pin "1") (pinfunction "E_1") (pintype "passive"))
    )
    (net (code "63") (name "Net-(Q3-G)") (class "Default")
      (node (ref "Q3") (pin "2") (pinfunction "G_2") (pintype "passive"))
      (node (ref "R10") (pin "2") (pinfunction "2_2") (pintype "passive"))
    )
    (net (code "64") (name "Net-(Q3-S)") (class "Default")
      (node (ref "J2") (pin "1") (pinfunction "1_1") (pintype "passive"))
      (node (ref "Q3") (pin "1") (pinfunction "S_1") (pintype "passive"))
    )
    (net (code "65") (name "Net-(R1-PadA)") (class "Default")
      (node (ref "R1") (pin "A") (pinfunction "A_A") (pintype "passive"))
      (node (ref "R2") (pin "1") (pinfunction "1_1") (pintype "passive"))
    )
    (net (code "66") (name "Net-(S2-S)") (class "Default")
      (node (ref "R19") (pin "1") (pinfunction "1_1") (pintype "passive"))
      (node (ref "S2") (pin "3") (pinfunction "S_3") (pintype "passive"))
    )
    (net (code "67") (name "unconnected-(IC6-(PCI0{slash}ICP{slash}CLKO)PB0-Pad14)") (class "Default")
      (node (ref "IC6") (pin "14") (pinfunction "(PCI0/ICP/CLKO)PB0_14") (pintype "bidirectional"))
    )
    (net (code "68") (name "unconnected-(IC6-(PCI3{slash}MOSI{slash}OC2A)PB3-Pad17)") (class "Default")
      (node (ref "IC6") (pin "17") (pinfunction "(PCI3/MOSI/OC2A)PB3_17") (pintype "bidirectional"))
    )
    (net (code "69") (name "unconnected-(IC6-(PCI9{slash}ADC1)PC1-Pad24)") (class "Default")
      (node (ref "IC6") (pin "24") (pinfunction "(PCI9/ADC1)PC1_24") (pintype "bidirectional"))
    )
    (net (code "70") (name "unconnected-(IC6-(PCI10{slash}ADC2)PC2-Pad25)") (class "Default")
      (node (ref "IC6") (pin "25") (pinfunction "(PCI10/ADC2)PC2_25") (pintype "bidirectional"))
    )
    (net (code "71") (name "unconnected-(IC6-(PCI11{slash}ADC3)PC3-Pad26)") (class "Default")
      (node (ref "IC6") (pin "26") (pinfunction "(PCI11/ADC3)PC3_26") (pintype "bidirectional"))
    )
    (net (code "72") (name "unconnected-(IC6-(PCI18{slash}INT0)PD2-Pad4)") (class "Default")
      (node (ref "IC6") (pin "4") (pinfunction "(PCI18/INT0)PD2_4") (pintype "bidirectional"))
    )
    (net (code "73") (name "unconnected-(IC6-(PCI19{slash}INT1{slash}OC2B)PD3-Pad5)") (class "Default")
      (node (ref "IC6") (pin "5") (pinfunction "(PCI19/INT1/OC2B)PD3_5") (pintype "bidirectional"))
    )
    (net (code "74") (name "unconnected-(IC6-(PCI20{slash}XCK{slash}T0)PD4-Pad6)") (class "Default")
      (node (ref "IC6") (pin "6") (pinfunction "(PCI20/XCK/T0)PD4_6") (pintype "bidirectional"))
    )
    (net (code "75") (name "unconnected-(IC6-(PCI21{slash}T1{slash}OC0B)PD5-Pad11)") (class "Default")
      (node (ref "IC6") (pin "11") (pinfunction "(PCI21/T1/OC0B)PD5_11") (pintype "bidirectional"))
    )
    (net (code "76") (name "unconnected-(IC6-(PCI22{slash}AIN0OC0A)PD6-Pad12)") (class "Default")
      (node (ref "IC6") (pin "12") (pinfunction "(PCI22/AIN0OC0A)PD6_12") (pintype "bidirectional"))
    )
    (net (code "77") (name "unconnected-(IC6-(PCI23{slash}AIN1)PD7-Pad13)") (class "Default")
      (node (ref "IC6") (pin "13") (pinfunction "(PCI23/AIN1)PD7_13") (pintype "bidirectional"))
    )
    (net (code "78") (name "unconnected-(IC7-INT-Pad8)") (class "Default")
      (node (ref "IC7") (pin "8") (pinfunction "INT_8") (pintype "output"))
    )
    (net (code "79") (name "unconnected-(IC8-INT-Pad8)") (class "Default")
      (node (ref "IC8") (pin "8") (pinfunction "INT_8") (pintype "output"))
    )
    (net (code "80") (name "unconnected-(IC9-INT-Pad8)") (class "Default")
      (node (ref "IC9") (pin "8") (pinfunction "INT_8") (pintype "output"))
    )
    (net (code "81") (name "unconnected-(IC10-CTS-Pad12)") (class "Default")
      (node (ref "IC10") (pin "12") (pinfunction "CTS_12") (pintype "output"))
    )
    (net (code "82") (name "unconnected-(IC10-DIO0-Pad20)") (class "Default")
      (node (ref "IC10") (pin "20") (pinfunction "DIO0_20") (pintype "bidirectional"))
    )
    (net (code "83") (name "unconnected-(IC10-DIO1-Pad19)") (class "Default")
      (node (ref "IC10") (pin "19") (pinfunction "DIO1_19") (pintype "bidirectional"))
    )
    (net (code "84") (name "unconnected-(IC10-DIO2-Pad18)") (class "Default")
      (node (ref "IC10") (pin "18") (pinfunction "DIO2_18") (pintype "bidirectional"))
    )
    (net (code "85") (name "unconnected-(IC10-DIO3-Pad17)") (class "Default")
      (node (ref "IC10") (pin "17") (pinfunction "DIO3_17") (pintype "bidirectional"))
    )
    (net (code "86") (name "unconnected-(IC10-DIO4-Pad11)") (class "Default")
      (node (ref "IC10") (pin "11") (pinfunction "DIO4_11") (pintype "bidirectional"))
    )
    (net (code "87") (name "unconnected-(IC10-DIO5-Pad15)") (class "Default")
      (node (ref "IC10") (pin "15") (pinfunction "DIO5_15") (pintype "bidirectional"))
    )
    (net (code "88") (name "unconnected-(IC10-DIO9-Pad13)") (class "Default")
      (node (ref "IC10") (pin "13") (pinfunction "DIO9_13") (pintype "bidirectional"))
    )
    (net (code "89") (name "unconnected-(IC10-DIO11-Pad7)") (class "Default")
      (node (ref "IC10") (pin "7") (pinfunction "DIO11_7") (pintype "bidirectional"))
    )
    (net (code "90") (name "unconnected-(IC10-DIO12-Pad4)") (class "Default")
      (node (ref "IC10") (pin "4") (pinfunction "DIO12_4") (pintype "bidirectional"))
    )
    (net (code "91") (name "unconnected-(IC10-DTR-Pad9)") (class "Default")
      (node (ref "IC10") (pin "9") (pinfunction "DTR_9") (pintype "bidirectional"))
    )
    (net (code "92") (name "unconnected-(IC10-RES-Pad14)") (class "Default")
      (node (ref "IC10") (pin "14") (pinfunction "RES_14") (pintype "bidirectional"))
    )
    (net (code "93") (name "unconnected-(IC10-RSSI-Pad6)") (class "Default")
      (node (ref "IC10") (pin "6") (pinfunction "RSSI_6") (pintype "bidirectional"))
    )
    (net (code "94") (name "unconnected-(IC10-RTS-Pad16)") (class "Default")
      (node (ref "IC10") (pin "16") (pinfunction "RTS_16") (pintype "input"))
    )
    (net (code "95") (name "unconnected-(J2-Pad2)") (class "Default")
      (node (ref "J2") (pin "2") (pinfunction "2_2") (pintype "passive"))
    )
    (net (code "96") (name "unconnected-(J2-Pad3)") (class "Default")
      (node (ref "J2") (pin "3") (pinfunction "3_3") (pintype "passive"))
    )
    (net (code "97") (name "unconnected-(J2-Pad4)") (class "Default")
      (node (ref "J2") (pin "4") (pinfunction "4_4") (pintype "passive"))
    )
    (net (code "98") (name "unconnected-(J3-Pad3)") (class "Default")
      (node (ref "J3") (pin "3") (pinfunction "3_3") (pintype "passive"))
    )
    (net (code "99") (name "unconnected-(J3-Pad4)") (class "Default")
      (node (ref "J3") (pin "4") (pinfunction "4_4") (pintype "passive"))
    )
    (net (code "100") (name "unconnected-(S2-O-Pad1)") (class "Default")
      (node (ref "S2") (pin "1") (pinfunction "O_1") (pintype "passive"))
    )
  )
)
